# 16n_13.net
KiCad netlist of a schematic drawn in EAGLE
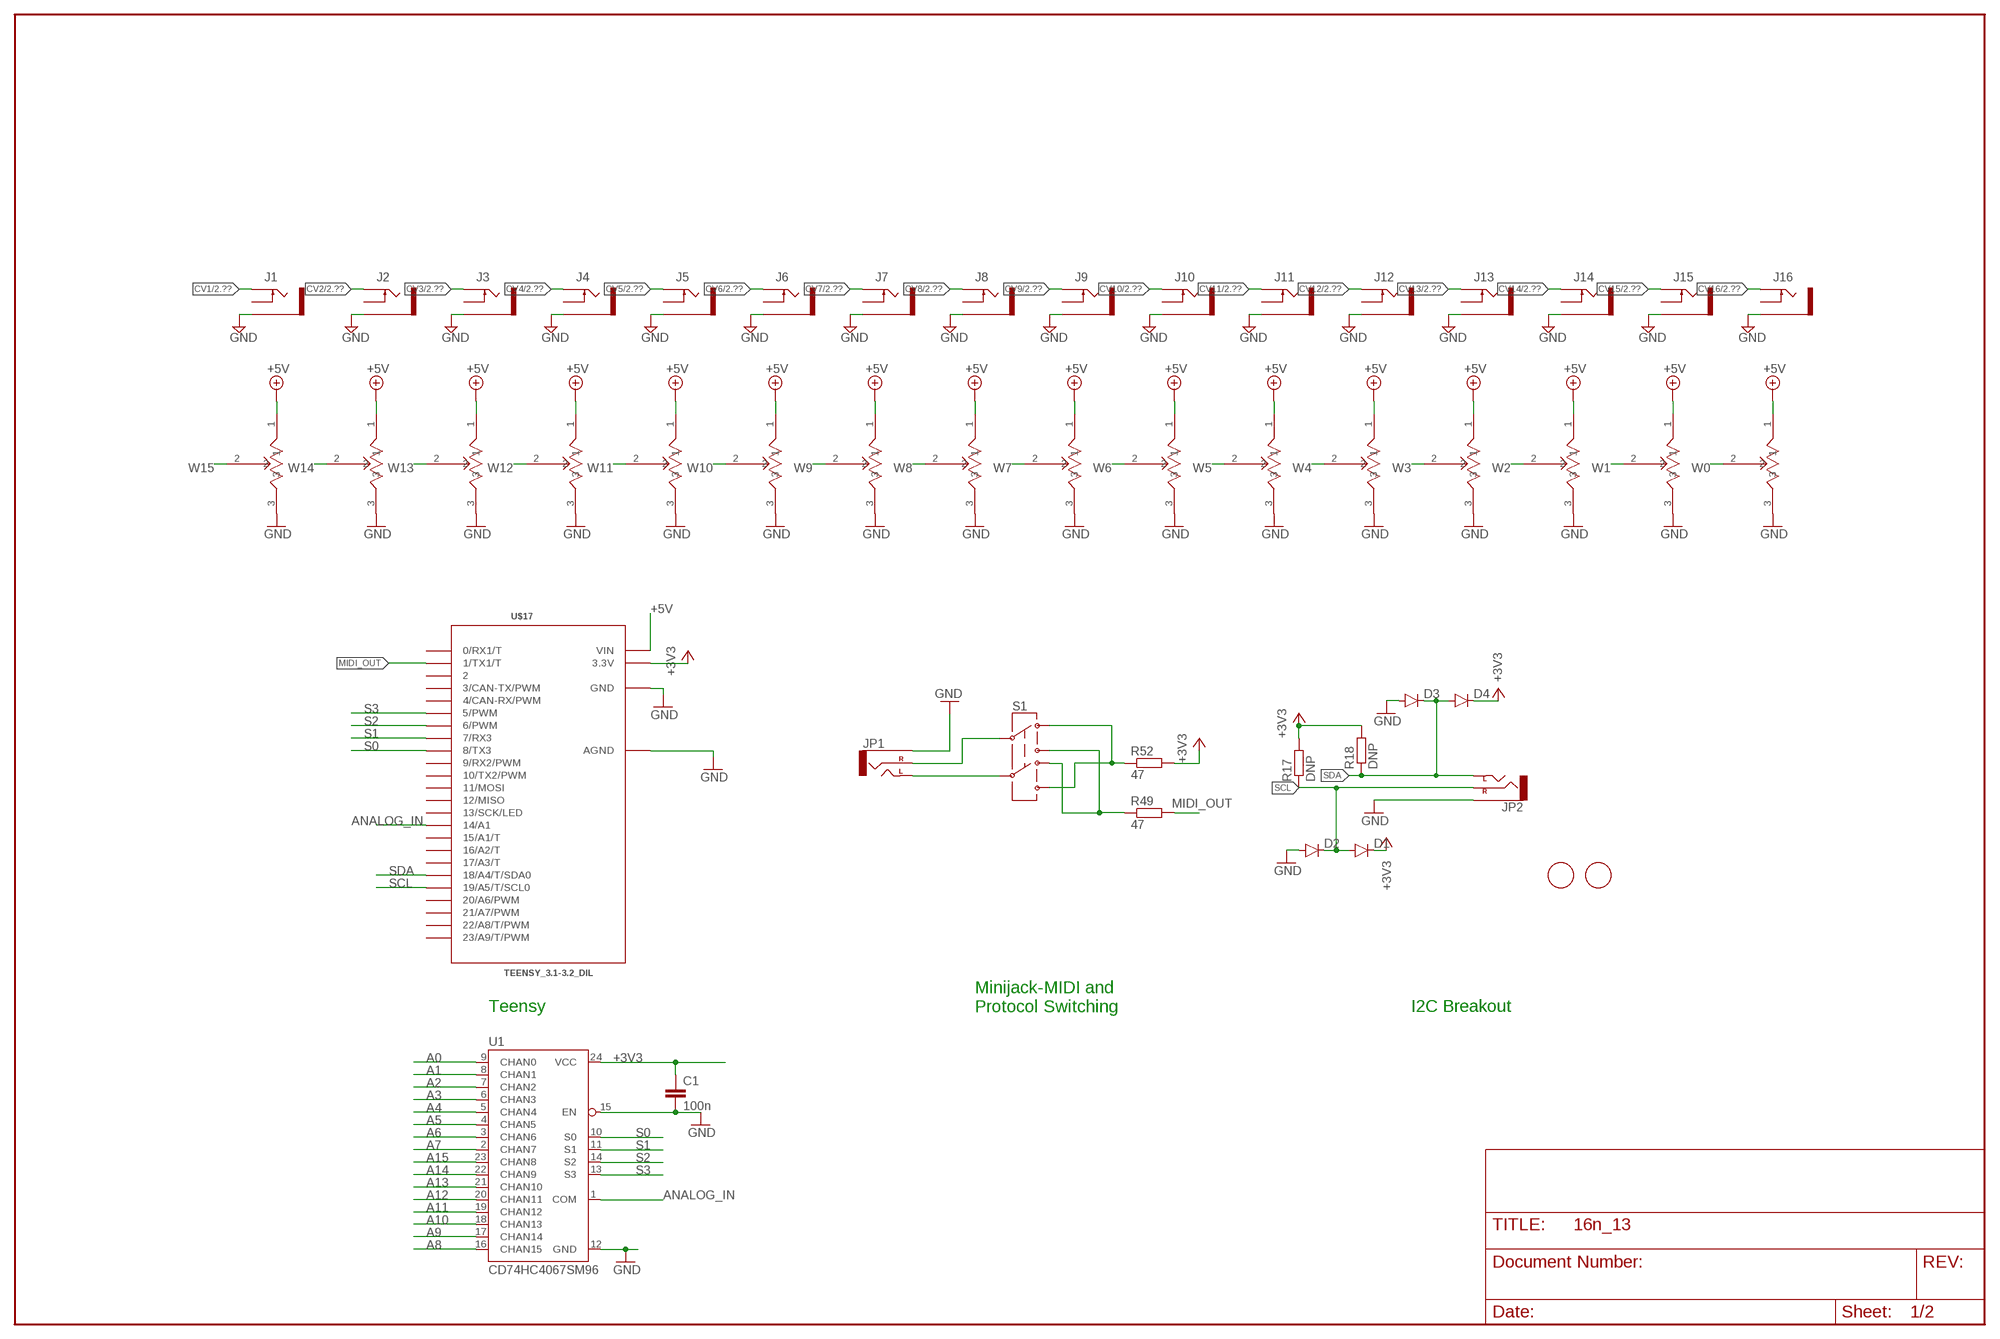
[diagram p0: schematic, sheet 1]
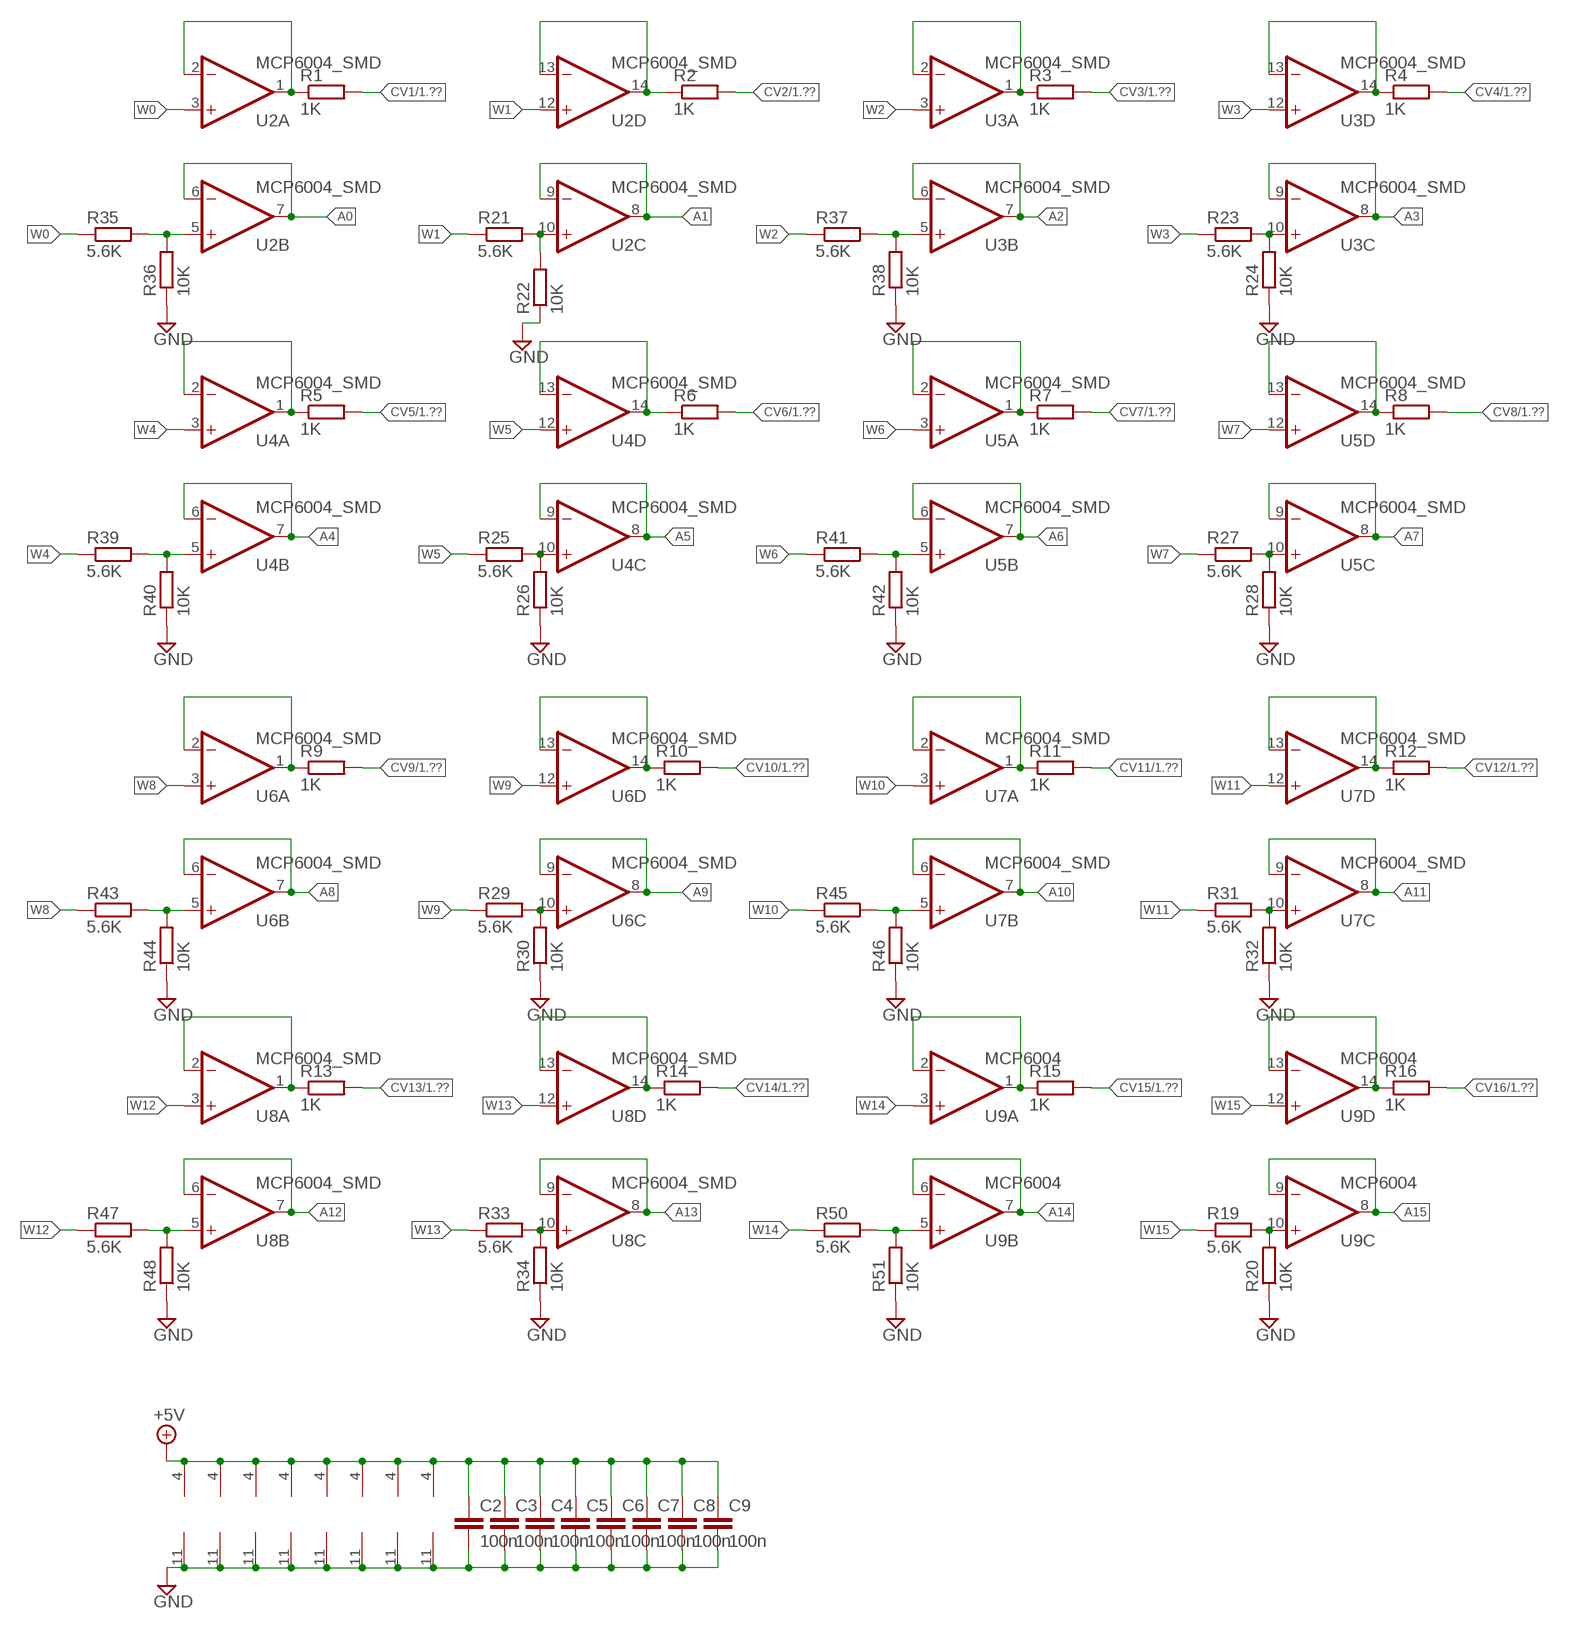
[diagram p1: schematic, sheet 2]

(export (version "E")
  (design (tool "Eeschema 10.0.6"))
  (components
    (comp (ref "C2")
      (value "100n")
      (footprint "eagle-import:C0805")
      (libsource (lib "eagle-import") (part "C-EUC0805"))
    )
    (comp (ref "C3")
      (value "100n")
      (footprint "eagle-import:C0805")
      (libsource (lib "eagle-import") (part "C-EUC0805"))
    )
    (comp (ref "C4")
      (value "100n")
      (footprint "eagle-import:C0805")
      (libsource (lib "eagle-import") (part "C-EUC0805"))
    )
    (comp (ref "C5")
      (value "100n")
      (footprint "eagle-import:C0805")
      (libsource (lib "eagle-import") (part "C-EUC0805"))
    )
    (comp (ref "C6")
      (value "100n")
      (footprint "eagle-import:C0805")
      (libsource (lib "eagle-import") (part "C-EUC0805"))
    )
    (comp (ref "C7")
      (value "100n")
      (footprint "eagle-import:C0805")
      (libsource (lib "eagle-import") (part "C-EUC0805"))
    )
    (comp (ref "C8")
      (value "100n")
      (footprint "eagle-import:C0805")
      (libsource (lib "eagle-import") (part "C-EUC0805"))
    )
    (comp (ref "C9")
      (value "100n")
      (footprint "eagle-import:C0805")
      (libsource (lib "eagle-import") (part "C-EUC0805"))
    )
    (comp (ref "R1")
      (value "1K")
      (footprint "eagle-import:R0805")
      (libsource (lib "eagle-import") (part "R-EU_R0805"))
    )
    (comp (ref "R2")
      (value "1K")
      (footprint "eagle-import:R0805")
      (libsource (lib "eagle-import") (part "R-EU_R0805"))
    )
    (comp (ref "R3")
      (value "1K")
      (footprint "eagle-import:R0805")
      (libsource (lib "eagle-import") (part "R-EU_R0805"))
    )
    (comp (ref "R4")
      (value "1K")
      (footprint "eagle-import:R0805")
      (libsource (lib "eagle-import") (part "R-EU_R0805"))
    )
    (comp (ref "R5")
      (value "1K")
      (footprint "eagle-import:R0805")
      (libsource (lib "eagle-import") (part "R-EU_R0805"))
    )
    (comp (ref "R6")
      (value "1K")
      (footprint "eagle-import:R0805")
      (libsource (lib "eagle-import") (part "R-EU_R0805"))
    )
    (comp (ref "R7")
      (value "1K")
      (footprint "eagle-import:R0805")
      (libsource (lib "eagle-import") (part "R-EU_R0805"))
    )
    (comp (ref "R8")
      (value "1K")
      (footprint "eagle-import:R0805")
      (libsource (lib "eagle-import") (part "R-EU_R0805"))
    )
    (comp (ref "R9")
      (value "1K")
      (footprint "eagle-import:R0805")
      (libsource (lib "eagle-import") (part "R-EU_R0805"))
    )
    (comp (ref "R10")
      (value "1K")
      (footprint "eagle-import:R0805")
      (libsource (lib "eagle-import") (part "R-EU_R0805"))
    )
    (comp (ref "R11")
      (value "1K")
      (footprint "eagle-import:R0805")
      (libsource (lib "eagle-import") (part "R-EU_R0805"))
    )
    (comp (ref "R12")
      (value "1K")
      (footprint "eagle-import:R0805")
      (libsource (lib "eagle-import") (part "R-EU_R0805"))
    )
    (comp (ref "R13")
      (value "1K")
      (footprint "eagle-import:R0805")
      (libsource (lib "eagle-import") (part "R-EU_R0805"))
    )
    (comp (ref "R14")
      (value "1K")
      (footprint "eagle-import:R0805")
      (libsource (lib "eagle-import") (part "R-EU_R0805"))
    )
    (comp (ref "R15")
      (value "1K")
      (footprint "eagle-import:R0805")
      (libsource (lib "eagle-import") (part "R-EU_R0805"))
    )
    (comp (ref "R16")
      (value "1K")
      (footprint "eagle-import:R0805")
      (libsource (lib "eagle-import") (part "R-EU_R0805"))
    )
    (comp (ref "R19")
      (value "5.6K")
      (footprint "eagle-import:R0805")
      (libsource (lib "eagle-import") (part "R-EU_R0805"))
    )
    (comp (ref "R20")
      (value "10K")
      (footprint "eagle-import:R0805")
      (libsource (lib "eagle-import") (part "R-EU_R0805"))
    )
    (comp (ref "R21")
      (value "5.6K")
      (footprint "eagle-import:R0805")
      (libsource (lib "eagle-import") (part "R-EU_R0805"))
    )
    (comp (ref "R22")
      (value "10K")
      (footprint "eagle-import:R0805")
      (libsource (lib "eagle-import") (part "R-EU_R0805"))
    )
    (comp (ref "R23")
      (value "5.6K")
      (footprint "eagle-import:R0805")
      (libsource (lib "eagle-import") (part "R-EU_R0805"))
    )
    (comp (ref "R24")
      (value "10K")
      (footprint "eagle-import:R0805")
      (libsource (lib "eagle-import") (part "R-EU_R0805"))
    )
    (comp (ref "R25")
      (value "5.6K")
      (footprint "eagle-import:R0805")
      (libsource (lib "eagle-import") (part "R-EU_R0805"))
    )
    (comp (ref "R26")
      (value "10K")
      (footprint "eagle-import:R0805")
      (libsource (lib "eagle-import") (part "R-EU_R0805"))
    )
    (comp (ref "R27")
      (value "5.6K")
      (footprint "eagle-import:R0805")
      (libsource (lib "eagle-import") (part "R-EU_R0805"))
    )
    (comp (ref "R28")
      (value "10K")
      (footprint "eagle-import:R0805")
      (libsource (lib "eagle-import") (part "R-EU_R0805"))
    )
    (comp (ref "R29")
      (value "5.6K")
      (footprint "eagle-import:R0805")
      (libsource (lib "eagle-import") (part "R-EU_R0805"))
    )
    (comp (ref "R30")
      (value "10K")
      (footprint "eagle-import:R0805")
      (libsource (lib "eagle-import") (part "R-EU_R0805"))
    )
    (comp (ref "R31")
      (value "5.6K")
      (footprint "eagle-import:R0805")
      (libsource (lib "eagle-import") (part "R-EU_R0805"))
    )
    (comp (ref "R32")
      (value "10K")
      (footprint "eagle-import:R0805")
      (libsource (lib "eagle-import") (part "R-EU_R0805"))
    )
    (comp (ref "R33")
      (value "5.6K")
      (footprint "eagle-import:R0805")
      (libsource (lib "eagle-import") (part "R-EU_R0805"))
    )
    (comp (ref "R34")
      (value "10K")
      (footprint "eagle-import:R0805")
      (libsource (lib "eagle-import") (part "R-EU_R0805"))
    )
    (comp (ref "R35")
      (value "5.6K")
      (footprint "eagle-import:R0805")
      (libsource (lib "eagle-import") (part "R-EU_R0805"))
    )
    (comp (ref "R36")
      (value "10K")
      (footprint "eagle-import:R0805")
      (libsource (lib "eagle-import") (part "R-EU_R0805"))
    )
    (comp (ref "R37")
      (value "5.6K")
      (footprint "eagle-import:R0805")
      (libsource (lib "eagle-import") (part "R-EU_R0805"))
    )
    (comp (ref "R38")
      (value "10K")
      (footprint "eagle-import:R0805")
      (libsource (lib "eagle-import") (part "R-EU_R0805"))
    )
    (comp (ref "R39")
      (value "5.6K")
      (footprint "eagle-import:R0805")
      (libsource (lib "eagle-import") (part "R-EU_R0805"))
    )
    (comp (ref "R40")
      (value "10K")
      (footprint "eagle-import:R0805")
      (libsource (lib "eagle-import") (part "R-EU_R0805"))
    )
    (comp (ref "R41")
      (value "5.6K")
      (footprint "eagle-import:R0805")
      (libsource (lib "eagle-import") (part "R-EU_R0805"))
    )
    (comp (ref "R42")
      (value "10K")
      (footprint "eagle-import:R0805")
      (libsource (lib "eagle-import") (part "R-EU_R0805"))
    )
    (comp (ref "R43")
      (value "5.6K")
      (footprint "eagle-import:R0805")
      (libsource (lib "eagle-import") (part "R-EU_R0805"))
    )
    (comp (ref "R44")
      (value "10K")
      (footprint "eagle-import:R0805")
      (libsource (lib "eagle-import") (part "R-EU_R0805"))
    )
    (comp (ref "R45")
      (value "5.6K")
      (footprint "eagle-import:R0805")
      (libsource (lib "eagle-import") (part "R-EU_R0805"))
    )
    (comp (ref "R46")
      (value "10K")
      (footprint "eagle-import:R0805")
      (libsource (lib "eagle-import") (part "R-EU_R0805"))
    )
    (comp (ref "R47")
      (value "5.6K")
      (footprint "eagle-import:R0805")
      (libsource (lib "eagle-import") (part "R-EU_R0805"))
    )
    (comp (ref "R48")
      (value "10K")
      (footprint "eagle-import:R0805")
      (libsource (lib "eagle-import") (part "R-EU_R0805"))
    )
    (comp (ref "R50")
      (value "5.6K")
      (footprint "eagle-import:R0805")
      (libsource (lib "eagle-import") (part "R-EU_R0805"))
    )
    (comp (ref "R51")
      (value "10K")
      (footprint "eagle-import:R0805")
      (libsource (lib "eagle-import") (part "R-EU_R0805"))
    )
    (comp (ref "U2")
      (value "MCP6004_SMD")
      (footprint "eagle-import:SO14")
      (libsource (lib "eagle-import") (part "MCP6004_SMD"))
    )
    (comp (ref "U3")
      (value "MCP6004_SMD")
      (footprint "eagle-import:SO14")
      (libsource (lib "eagle-import") (part "MCP6004_SMD"))
    )
    (comp (ref "U4")
      (value "MCP6004_SMD")
      (footprint "eagle-import:SO14")
      (libsource (lib "eagle-import") (part "MCP6004_SMD"))
    )
    (comp (ref "U5")
      (value "MCP6004_SMD")
      (footprint "eagle-import:SO14")
      (libsource (lib "eagle-import") (part "MCP6004_SMD"))
    )
    (comp (ref "U6")
      (value "MCP6004_SMD")
      (footprint "eagle-import:SO14")
      (libsource (lib "eagle-import") (part "MCP6004_SMD"))
    )
    (comp (ref "U7")
      (value "MCP6004_SMD")
      (footprint "eagle-import:SO14")
      (libsource (lib "eagle-import") (part "MCP6004_SMD"))
    )
    (comp (ref "U8")
      (value "MCP6004_SMD")
      (footprint "eagle-import:SO14")
      (libsource (lib "eagle-import") (part "MCP6004_SMD"))
    )
    (comp (ref "U9")
      (value "MCP6004")
      (footprint "eagle-import:SO14")
      (libsource (lib "eagle-import") (part "MCP6004_SMD"))
    )
    (comp (ref "C1")
      (value "100n")
      (footprint "eagle-import:C0805")
      (libsource (lib "eagle-import") (part "C-EUC0805"))
    )
    (comp (ref "D1")
      (value "DIODESOD123")
      (footprint "eagle-import:SOD-123")
      (libsource (lib "eagle-import") (part "DIODESOD123"))
    )
    (comp (ref "D2")
      (value "DIODESOD123")
      (footprint "eagle-import:SOD-123")
      (libsource (lib "eagle-import") (part "DIODESOD123"))
    )
    (comp (ref "D3")
      (value "DIODESOD123")
      (footprint "eagle-import:SOD-123")
      (libsource (lib "eagle-import") (part "DIODESOD123"))
    )
    (comp (ref "D4")
      (value "DIODESOD123")
      (footprint "eagle-import:SOD-123")
      (libsource (lib "eagle-import") (part "DIODESOD123"))
    )
    (comp (ref "FID1")
      (value "FIDUCIAL")
      (footprint "eagle-import:FIDUCIAL_1MM")
      (libsource (lib "eagle-import") (part "FIDUCIAL"))
    )
    (comp (ref "FID2")
      (value "FIDUCIAL")
      (footprint "eagle-import:FIDUCIAL_1MM")
      (libsource (lib "eagle-import") (part "FIDUCIAL"))
    )
    (comp (ref "J1")
      (value "PJ302M")
      (footprint "eagle-import:PJ302M")
      (libsource (lib "eagle-import") (part "PJ302M"))
    )
    (comp (ref "J2")
      (value "PJ302M")
      (footprint "eagle-import:PJ302M")
      (libsource (lib "eagle-import") (part "PJ302M"))
    )
    (comp (ref "J3")
      (value "PJ302M")
      (footprint "eagle-import:PJ302M")
      (libsource (lib "eagle-import") (part "PJ302M"))
    )
    (comp (ref "J4")
      (value "PJ302M")
      (footprint "eagle-import:PJ302M")
      (libsource (lib "eagle-import") (part "PJ302M"))
    )
    (comp (ref "J5")
      (value "PJ302M")
      (footprint "eagle-import:PJ302M")
      (libsource (lib "eagle-import") (part "PJ302M"))
    )
    (comp (ref "J6")
      (value "PJ302M")
      (footprint "eagle-import:PJ302M")
      (libsource (lib "eagle-import") (part "PJ302M"))
    )
    (comp (ref "J7")
      (value "PJ302M")
      (footprint "eagle-import:PJ302M")
      (libsource (lib "eagle-import") (part "PJ302M"))
    )
    (comp (ref "J8")
      (value "PJ302M")
      (footprint "eagle-import:PJ302M")
      (libsource (lib "eagle-import") (part "PJ302M"))
    )
    (comp (ref "J9")
      (value "PJ302M")
      (footprint "eagle-import:PJ302M")
      (libsource (lib "eagle-import") (part "PJ302M"))
    )
    (comp (ref "J10")
      (value "PJ302M")
      (footprint "eagle-import:PJ302M")
      (libsource (lib "eagle-import") (part "PJ302M"))
    )
    (comp (ref "J11")
      (value "PJ302M")
      (footprint "eagle-import:PJ302M")
      (libsource (lib "eagle-import") (part "PJ302M"))
    )
    (comp (ref "J12")
      (value "PJ302M")
      (footprint "eagle-import:PJ302M")
      (libsource (lib "eagle-import") (part "PJ302M"))
    )
    (comp (ref "J13")
      (value "PJ302M")
      (footprint "eagle-import:PJ302M")
      (libsource (lib "eagle-import") (part "PJ302M"))
    )
    (comp (ref "J14")
      (value "PJ302M")
      (footprint "eagle-import:PJ302M")
      (libsource (lib "eagle-import") (part "PJ302M"))
    )
    (comp (ref "J15")
      (value "PJ302M")
      (footprint "eagle-import:PJ302M")
      (libsource (lib "eagle-import") (part "PJ302M"))
    )
    (comp (ref "J16")
      (value "PJ302M")
      (footprint "eagle-import:PJ302M")
      (libsource (lib "eagle-import") (part "PJ302M"))
    )
    (comp (ref "JP1")
      (value "AUDIO-JACKPTH")
      (footprint "eagle-import:AUDIO-JACK")
      (libsource (lib "eagle-import") (part "AUDIO-JACKPTH"))
    )
    (comp (ref "JP2")
      (value "AUDIO-JACKPTH")
      (footprint "eagle-import:AUDIO-JACK")
      (libsource (lib "eagle-import") (part "AUDIO-JACKPTH"))
    )
    (comp (ref "R17")
      (value "DNP")
      (footprint "eagle-import:R0805")
      (libsource (lib "eagle-import") (part "R-EU_R0805"))
    )
    (comp (ref "R18")
      (value "DNP")
      (footprint "eagle-import:R0805")
      (libsource (lib "eagle-import") (part "R-EU_R0805"))
    )
    (comp (ref "R49")
      (value "47")
      (footprint "eagle-import:R0805")
      (libsource (lib "eagle-import") (part "R-EU_R0805"))
    )
    (comp (ref "R52")
      (value "47")
      (footprint "eagle-import:R0805")
      (libsource (lib "eagle-import") (part "R-EU_R0805"))
    )
    (comp (ref "S1")
      (value "SWITCH-DPDTEG2211")
      (footprint "eagle-import:EG2211")
      (libsource (lib "eagle-import") (part "SWITCH-DPDTEG2211"))
    )
    (comp (ref "U$1")
      (value "SLIDEPOT-ALPS-60MM")
      (footprint "eagle-import:RS6011SP600")
      (libsource (lib "eagle-import") (part "SLIDEPOT-ALPS-60MM"))
    )
    (comp (ref "U$2")
      (value "SLIDEPOT-ALPS-60MM")
      (footprint "eagle-import:RS6011SP600")
      (libsource (lib "eagle-import") (part "SLIDEPOT-ALPS-60MM"))
    )
    (comp (ref "U$3")
      (value "SLIDEPOT-ALPS-60MM")
      (footprint "eagle-import:RS6011SP600")
      (libsource (lib "eagle-import") (part "SLIDEPOT-ALPS-60MM"))
    )
    (comp (ref "U$4")
      (value "SLIDEPOT-ALPS-60MM")
      (footprint "eagle-import:RS6011SP600")
      (libsource (lib "eagle-import") (part "SLIDEPOT-ALPS-60MM"))
    )
    (comp (ref "U$5")
      (value "SLIDEPOT-ALPS-60MM")
      (footprint "eagle-import:RS6011SP600")
      (libsource (lib "eagle-import") (part "SLIDEPOT-ALPS-60MM"))
    )
    (comp (ref "U$6")
      (value "SLIDEPOT-ALPS-60MM")
      (footprint "eagle-import:RS6011SP600")
      (libsource (lib "eagle-import") (part "SLIDEPOT-ALPS-60MM"))
    )
    (comp (ref "U$7")
      (value "SLIDEPOT-ALPS-60MM")
      (footprint "eagle-import:RS6011SP600")
      (libsource (lib "eagle-import") (part "SLIDEPOT-ALPS-60MM"))
    )
    (comp (ref "U$8")
      (value "SLIDEPOT-ALPS-60MM")
      (footprint "eagle-import:RS6011SP600")
      (libsource (lib "eagle-import") (part "SLIDEPOT-ALPS-60MM"))
    )
    (comp (ref "U$9")
      (value "SLIDEPOT-ALPS-60MM")
      (footprint "eagle-import:RS6011SP600")
      (libsource (lib "eagle-import") (part "SLIDEPOT-ALPS-60MM"))
    )
    (comp (ref "U$10")
      (value "SLIDEPOT-ALPS-60MM")
      (footprint "eagle-import:RS6011SP600")
      (libsource (lib "eagle-import") (part "SLIDEPOT-ALPS-60MM"))
    )
    (comp (ref "U$11")
      (value "SLIDEPOT-ALPS-60MM")
      (footprint "eagle-import:RS6011SP600")
      (libsource (lib "eagle-import") (part "SLIDEPOT-ALPS-60MM"))
    )
    (comp (ref "U$12")
      (value "SLIDEPOT-ALPS-60MM")
      (footprint "eagle-import:RS6011SP600")
      (libsource (lib "eagle-import") (part "SLIDEPOT-ALPS-60MM"))
    )
    (comp (ref "U$13")
      (value "SLIDEPOT-ALPS-60MM")
      (footprint "eagle-import:RS6011SP600")
      (libsource (lib "eagle-import") (part "SLIDEPOT-ALPS-60MM"))
    )
    (comp (ref "U$14")
      (value "SLIDEPOT-ALPS-60MM")
      (footprint "eagle-import:RS6011SP600")
      (libsource (lib "eagle-import") (part "SLIDEPOT-ALPS-60MM"))
    )
    (comp (ref "U$15")
      (value "SLIDEPOT-ALPS-60MM")
      (footprint "eagle-import:RS6011SP600")
      (libsource (lib "eagle-import") (part "SLIDEPOT-ALPS-60MM"))
    )
    (comp (ref "U$16")
      (value "SLIDEPOT-ALPS-60MM")
      (footprint "eagle-import:RS6011SP600")
      (libsource (lib "eagle-import") (part "SLIDEPOT-ALPS-60MM"))
    )
    (comp (ref "U$17")
      (value "TEENSY_3.1-3.2_DIL")
      (footprint "eagle-import:TEENSY_3.0-3.2&LC_DIL")
      (libsource (lib "eagle-import") (part "TEENSY_3.1-3.2_DIL"))
    )
    (comp (ref "U1")
      (value "CD74HC4067SM96")
      (footprint "eagle-import:SOIC127P1030X265-24")
      (libsource (lib "eagle-import") (part "744067SO24"))
    )
  )
  (nets
    (net (code "1") (name "+3V3") (class "Default")
      (node (ref "C1") (pin "1") (pinfunction "1_1") (pintype "passive"))
      (node (ref "D1") (pin "C") (pinfunction "C_C") (pintype "passive"))
      (node (ref "D4") (pin "C") (pinfunction "C_C") (pintype "passive"))
      (node (ref "R17") (pin "2") (pinfunction "2_2") (pintype "passive"))
      (node (ref "R18") (pin "2") (pinfunction "2_2") (pintype "passive"))
      (node (ref "R52") (pin "2") (pinfunction "2_2") (pintype "passive"))
      (node (ref "U$17") (pin "3.3V") (pinfunction "3.3V_3.3V") (pintype "power_in"))
      (node (ref "U1") (pin "24") (pinfunction "VCC_24") (pintype "bidirectional"))
    )
    (net (code "2") (name "+5V") (class "Default")
      (node (ref "C2") (pin "1") (pinfunction "1_1") (pintype "passive"))
      (node (ref "C3") (pin "1") (pinfunction "1_1") (pintype "passive"))
      (node (ref "C4") (pin "1") (pinfunction "1_1") (pintype "passive"))
      (node (ref "C5") (pin "1") (pinfunction "1_1") (pintype "passive"))
      (node (ref "C6") (pin "1") (pinfunction "1_1") (pintype "passive"))
      (node (ref "C7") (pin "1") (pinfunction "1_1") (pintype "passive"))
      (node (ref "C8") (pin "1") (pinfunction "1_1") (pintype "passive"))
      (node (ref "C9") (pin "1") (pinfunction "1_1") (pintype "passive"))
      (node (ref "U$1") (pin "1") (pinfunction "1_1") (pintype "bidirectional"))
      (node (ref "U$10") (pin "1") (pinfunction "1_1") (pintype "bidirectional"))
      (node (ref "U$11") (pin "1") (pinfunction "1_1") (pintype "bidirectional"))
      (node (ref "U$12") (pin "1") (pinfunction "1_1") (pintype "bidirectional"))
      (node (ref "U$13") (pin "1") (pinfunction "1_1") (pintype "bidirectional"))
      (node (ref "U$14") (pin "1") (pinfunction "1_1") (pintype "bidirectional"))
      (node (ref "U$15") (pin "1") (pinfunction "1_1") (pintype "bidirectional"))
      (node (ref "U$16") (pin "1") (pinfunction "1_1") (pintype "bidirectional"))
      (node (ref "U$17") (pin "VIN") (pinfunction "VIN_VIN") (pintype "power_in"))
      (node (ref "U$2") (pin "1") (pinfunction "1_1") (pintype "bidirectional"))
      (node (ref "U$3") (pin "1") (pinfunction "1_1") (pintype "bidirectional"))
      (node (ref "U$4") (pin "1") (pinfunction "1_1") (pintype "bidirectional"))
      (node (ref "U$5") (pin "1") (pinfunction "1_1") (pintype "bidirectional"))
      (node (ref "U$6") (pin "1") (pinfunction "1_1") (pintype "bidirectional"))
      (node (ref "U$7") (pin "1") (pinfunction "1_1") (pintype "bidirectional"))
      (node (ref "U$8") (pin "1") (pinfunction "1_1") (pintype "bidirectional"))
      (node (ref "U$9") (pin "1") (pinfunction "1_1") (pintype "bidirectional"))
      (node (ref "U2") (pin "4") (pinfunction "V+_4") (pintype "power_in"))
      (node (ref "U3") (pin "4") (pinfunction "V+_4") (pintype "power_in"))
      (node (ref "U4") (pin "4") (pinfunction "V+_4") (pintype "power_in"))
      (node (ref "U5") (pin "4") (pinfunction "V+_4") (pintype "power_in"))
      (node (ref "U6") (pin "4") (pinfunction "V+_4") (pintype "power_in"))
      (node (ref "U7") (pin "4") (pinfunction "V+_4") (pintype "power_in"))
      (node (ref "U8") (pin "4") (pinfunction "V+_4") (pintype "power_in"))
      (node (ref "U9") (pin "4") (pinfunction "V+_4") (pintype "power_in"))
    )
    (net (code "3") (name "A0") (class "Default")
      (node (ref "U1") (pin "9") (pinfunction "CHAN0_9") (pintype "bidirectional"))
      (node (ref "U2") (pin "6") (pinfunction "-IN_6") (pintype "input"))
      (node (ref "U2") (pin "7") (pinfunction "OUT_7") (pintype "output"))
    )
    (net (code "4") (name "A1") (class "Default")
      (node (ref "U1") (pin "8") (pinfunction "CHAN1_8") (pintype "bidirectional"))
      (node (ref "U2") (pin "8") (pinfunction "OUT_8") (pintype "output"))
      (node (ref "U2") (pin "9") (pinfunction "-IN_9") (pintype "input"))
    )
    (net (code "5") (name "A2") (class "Default")
      (node (ref "U1") (pin "7") (pinfunction "CHAN2_7") (pintype "bidirectional"))
      (node (ref "U3") (pin "6") (pinfunction "-IN_6") (pintype "input"))
      (node (ref "U3") (pin "7") (pinfunction "OUT_7") (pintype "output"))
    )
    (net (code "6") (name "A3") (class "Default")
      (node (ref "U1") (pin "6") (pinfunction "CHAN3_6") (pintype "bidirectional"))
      (node (ref "U3") (pin "8") (pinfunction "OUT_8") (pintype "output"))
      (node (ref "U3") (pin "9") (pinfunction "-IN_9") (pintype "input"))
    )
    (net (code "7") (name "A4") (class "Default")
      (node (ref "U1") (pin "5") (pinfunction "CHAN4_5") (pintype "bidirectional"))
      (node (ref "U4") (pin "6") (pinfunction "-IN_6") (pintype "input"))
      (node (ref "U4") (pin "7") (pinfunction "OUT_7") (pintype "output"))
    )
    (net (code "8") (name "A5") (class "Default")
      (node (ref "U1") (pin "4") (pinfunction "CHAN5_4") (pintype "bidirectional"))
      (node (ref "U4") (pin "8") (pinfunction "OUT_8") (pintype "output"))
      (node (ref "U4") (pin "9") (pinfunction "-IN_9") (pintype "input"))
    )
    (net (code "9") (name "A6") (class "Default")
      (node (ref "U1") (pin "3") (pinfunction "CHAN6_3") (pintype "bidirectional"))
      (node (ref "U5") (pin "6") (pinfunction "-IN_6") (pintype "input"))
      (node (ref "U5") (pin "7") (pinfunction "OUT_7") (pintype "output"))
    )
    (net (code "10") (name "A7") (class "Default")
      (node (ref "U1") (pin "2") (pinfunction "CHAN7_2") (pintype "bidirectional"))
      (node (ref "U5") (pin "8") (pinfunction "OUT_8") (pintype "output"))
      (node (ref "U5") (pin "9") (pinfunction "-IN_9") (pintype "input"))
    )
    (net (code "11") (name "A8") (class "Default")
      (node (ref "U1") (pin "16") (pinfunction "CHAN15_16") (pintype "bidirectional"))
      (node (ref "U6") (pin "6") (pinfunction "-IN_6") (pintype "input"))
      (node (ref "U6") (pin "7") (pinfunction "OUT_7") (pintype "output"))
    )
    (net (code "12") (name "A9") (class "Default")
      (node (ref "U1") (pin "17") (pinfunction "CHAN14_17") (pintype "bidirectional"))
      (node (ref "U6") (pin "8") (pinfunction "OUT_8") (pintype "output"))
      (node (ref "U6") (pin "9") (pinfunction "-IN_9") (pintype "input"))
    )
    (net (code "13") (name "A10") (class "Default")
      (node (ref "U1") (pin "18") (pinfunction "CHAN13_18") (pintype "bidirectional"))
      (node (ref "U7") (pin "6") (pinfunction "-IN_6") (pintype "input"))
      (node (ref "U7") (pin "7") (pinfunction "OUT_7") (pintype "output"))
    )
    (net (code "14") (name "A11") (class "Default")
      (node (ref "U1") (pin "19") (pinfunction "CHAN12_19") (pintype "bidirectional"))
      (node (ref "U7") (pin "8") (pinfunction "OUT_8") (pintype "output"))
      (node (ref "U7") (pin "9") (pinfunction "-IN_9") (pintype "input"))
    )
    (net (code "15") (name "A12") (class "Default")
      (node (ref "U1") (pin "20") (pinfunction "CHAN11_20") (pintype "bidirectional"))
      (node (ref "U8") (pin "6") (pinfunction "-IN_6") (pintype "input"))
      (node (ref "U8") (pin "7") (pinfunction "OUT_7") (pintype "output"))
    )
    (net (code "16") (name "A13") (class "Default")
      (node (ref "U1") (pin "21") (pinfunction "CHAN10_21") (pintype "bidirectional"))
      (node (ref "U8") (pin "8") (pinfunction "OUT_8") (pintype "output"))
      (node (ref "U8") (pin "9") (pinfunction "-IN_9") (pintype "input"))
    )
    (net (code "17") (name "A14") (class "Default")
      (node (ref "U1") (pin "22") (pinfunction "CHAN9_22") (pintype "bidirectional"))
      (node (ref "U9") (pin "6") (pinfunction "-IN_6") (pintype "input"))
      (node (ref "U9") (pin "7") (pinfunction "OUT_7") (pintype "output"))
    )
    (net (code "18") (name "A15") (class "Default")
      (node (ref "U1") (pin "23") (pinfunction "CHAN8_23") (pintype "bidirectional"))
      (node (ref "U9") (pin "8") (pinfunction "OUT_8") (pintype "output"))
      (node (ref "U9") (pin "9") (pinfunction "-IN_9") (pintype "input"))
    )
    (net (code "19") (name "ANALOG_IN") (class "Default")
      (node (ref "U$17") (pin "14/A0") (pinfunction "14/A1_14/A0") (pintype "bidirectional"))
      (node (ref "U1") (pin "1") (pinfunction "COM_1") (pintype "bidirectional"))
    )
    (net (code "20") (name "CV1") (class "Default")
      (node (ref "J1") (pin "TIP") (pinfunction "TIP_TIP") (pintype "passive"))
      (node (ref "R1") (pin "2") (pinfunction "2_2") (pintype "passive"))
    )
    (net (code "21") (name "CV2") (class "Default")
      (node (ref "J2") (pin "TIP") (pinfunction "TIP_TIP") (pintype "passive"))
      (node (ref "R2") (pin "2") (pinfunction "2_2") (pintype "passive"))
    )
    (net (code "22") (name "CV3") (class "Default")
      (node (ref "J3") (pin "TIP") (pinfunction "TIP_TIP") (pintype "passive"))
      (node (ref "R3") (pin "2") (pinfunction "2_2") (pintype "passive"))
    )
    (net (code "23") (name "CV4") (class "Default")
      (node (ref "J4") (pin "TIP") (pinfunction "TIP_TIP") (pintype "passive"))
      (node (ref "R4") (pin "2") (pinfunction "2_2") (pintype "passive"))
    )
    (net (code "24") (name "CV5") (class "Default")
      (node (ref "J5") (pin "TIP") (pinfunction "TIP_TIP") (pintype "passive"))
      (node (ref "R5") (pin "2") (pinfunction "2_2") (pintype "passive"))
    )
    (net (code "25") (name "CV6") (class "Default")
      (node (ref "J6") (pin "TIP") (pinfunction "TIP_TIP") (pintype "passive"))
      (node (ref "R6") (pin "2") (pinfunction "2_2") (pintype "passive"))
    )
    (net (code "26") (name "CV7") (class "Default")
      (node (ref "J7") (pin "TIP") (pinfunction "TIP_TIP") (pintype "passive"))
      (node (ref "R7") (pin "2") (pinfunction "2_2") (pintype "passive"))
    )
    (net (code "27") (name "CV8") (class "Default")
      (node (ref "J8") (pin "TIP") (pinfunction "TIP_TIP") (pintype "passive"))
      (node (ref "R8") (pin "2") (pinfunction "2_2") (pintype "passive"))
    )
    (net (code "28") (name "CV9") (class "Default")
      (node (ref "J9") (pin "TIP") (pinfunction "TIP_TIP") (pintype "passive"))
      (node (ref "R9") (pin "2") (pinfunction "2_2") (pintype "passive"))
    )
    (net (code "29") (name "CV10") (class "Default")
      (node (ref "J10") (pin "TIP") (pinfunction "TIP_TIP") (pintype "passive"))
      (node (ref "R10") (pin "2") (pinfunction "2_2") (pintype "passive"))
    )
    (net (code "30") (name "CV11") (class "Default")
      (node (ref "J11") (pin "TIP") (pinfunction "TIP_TIP") (pintype "passive"))
      (node (ref "R11") (pin "2") (pinfunction "2_2") (pintype "passive"))
    )
    (net (code "31") (name "CV12") (class "Default")
      (node (ref "J12") (pin "TIP") (pinfunction "TIP_TIP") (pintype "passive"))
      (node (ref "R12") (pin "2") (pinfunction "2_2") (pintype "passive"))
    )
    (net (code "32") (name "CV13") (class "Default")
      (node (ref "J13") (pin "TIP") (pinfunction "TIP_TIP") (pintype "passive"))
      (node (ref "R13") (pin "2") (pinfunction "2_2") (pintype "passive"))
    )
    (net (code "33") (name "CV14") (class "Default")
      (node (ref "J14") (pin "TIP") (pinfunction "TIP_TIP") (pintype "passive"))
      (node (ref "R14") (pin "2") (pinfunction "2_2") (pintype "passive"))
    )
    (net (code "34") (name "CV15") (class "Default")
      (node (ref "J15") (pin "TIP") (pinfunction "TIP_TIP") (pintype "passive"))
      (node (ref "R15") (pin "2") (pinfunction "2_2") (pintype "passive"))
    )
    (net (code "35") (name "CV16") (class "Default")
      (node (ref "J16") (pin "TIP") (pinfunction "TIP_TIP") (pintype "passive"))
      (node (ref "R16") (pin "2") (pinfunction "2_2") (pintype "passive"))
    )
    (net (code "36") (name "GND") (class "Default")
      (node (ref "C1") (pin "2") (pinfunction "2_2") (pintype "passive"))
      (node (ref "C2") (pin "2") (pinfunction "2_2") (pintype "passive"))
      (node (ref "C3") (pin "2") (pinfunction "2_2") (pintype "passive"))
      (node (ref "C4") (pin "2") (pinfunction "2_2") (pintype "passive"))
      (node (ref "C5") (pin "2") (pinfunction "2_2") (pintype "passive"))
      (node (ref "C6") (pin "2") (pinfunction "2_2") (pintype "passive"))
      (node (ref "C7") (pin "2") (pinfunction "2_2") (pintype "passive"))
      (node (ref "C8") (pin "2") (pinfunction "2_2") (pintype "passive"))
      (node (ref "C9") (pin "2") (pinfunction "2_2") (pintype "passive"))
      (node (ref "D2") (pin "A") (pinfunction "A_A") (pintype "passive"))
      (node (ref "D3") (pin "A") (pinfunction "A_A") (pintype "passive"))
      (node (ref "J1") (pin "GND") (pinfunction "SLEEVE_GND") (pintype "passive"))
      (node (ref "J10") (pin "GND") (pinfunction "SLEEVE_GND") (pintype "passive"))
      (node (ref "J11") (pin "GND") (pinfunction "SLEEVE_GND") (pintype "passive"))
      (node (ref "J12") (pin "GND") (pinfunction "SLEEVE_GND") (pintype "passive"))
      (node (ref "J13") (pin "GND") (pinfunction "SLEEVE_GND") (pintype "passive"))
      (node (ref "J14") (pin "GND") (pinfunction "SLEEVE_GND") (pintype "passive"))
      (node (ref "J15") (pin "GND") (pinfunction "SLEEVE_GND") (pintype "passive"))
      (node (ref "J16") (pin "GND") (pinfunction "SLEEVE_GND") (pintype "passive"))
      (node (ref "J2") (pin "GND") (pinfunction "SLEEVE_GND") (pintype "passive"))
      (node (ref "J3") (pin "GND") (pinfunction "SLEEVE_GND") (pintype "passive"))
      (node (ref "J4") (pin "GND") (pinfunction "SLEEVE_GND") (pintype "passive"))
      (node (ref "J5") (pin "GND") (pinfunction "SLEEVE_GND") (pintype "passive"))
      (node (ref "J6") (pin "GND") (pinfunction "SLEEVE_GND") (pintype "passive"))
      (node (ref "J7") (pin "GND") (pinfunction "SLEEVE_GND") (pintype "passive"))
      (node (ref "J8") (pin "GND") (pinfunction "SLEEVE_GND") (pintype "passive"))
      (node (ref "J9") (pin "GND") (pinfunction "SLEEVE_GND") (pintype "passive"))
      (node (ref "JP1") (pin "SLEEVE") (pinfunction "SLEEVE_SLEEVE") (pintype "bidirectional"))
      (node (ref "JP2") (pin "SLEEVE") (pinfunction "SLEEVE_SLEEVE") (pintype "bidirectional"))
      (node (ref "R20") (pin "1") (pinfunction "1_1") (pintype "passive"))
      (node (ref "R22") (pin "1") (pinfunction "1_1") (pintype "passive"))
      (node (ref "R24") (pin "1") (pinfunction "1_1") (pintype "passive"))
      (node (ref "R26") (pin "1") (pinfunction "1_1") (pintype "passive"))
      (node (ref "R28") (pin "1") (pinfunction "1_1") (pintype "passive"))
      (node (ref "R30") (pin "1") (pinfunction "1_1") (pintype "passive"))
      (node (ref "R32") (pin "1") (pinfunction "1_1") (pintype "passive"))
      (node (ref "R34") (pin "1") (pinfunction "1_1") (pintype "passive"))
      (node (ref "R36") (pin "1") (pinfunction "1_1") (pintype "passive"))
      (node (ref "R38") (pin "1") (pinfunction "1_1") (pintype "passive"))
      (node (ref "R40") (pin "1") (pinfunction "1_1") (pintype "passive"))
      (node (ref "R42") (pin "1") (pinfunction "1_1") (pintype "passive"))
      (node (ref "R44") (pin "1") (pinfunction "1_1") (pintype "passive"))
      (node (ref "R46") (pin "1") (pinfunction "1_1") (pintype "passive"))
      (node (ref "R48") (pin "1") (pinfunction "1_1") (pintype "passive"))
      (node (ref "R51") (pin "1") (pinfunction "1_1") (pintype "passive"))
      (node (ref "U$1") (pin "3") (pinfunction "3_3") (pintype "bidirectional"))
      (node (ref "U$10") (pin "3") (pinfunction "3_3") (pintype "bidirectional"))
      (node (ref "U$11") (pin "3") (pinfunction "3_3") (pintype "bidirectional"))
      (node (ref "U$12") (pin "3") (pinfunction "3_3") (pintype "bidirectional"))
      (node (ref "U$13") (pin "3") (pinfunction "3_3") (pintype "bidirectional"))
      (node (ref "U$14") (pin "3") (pinfunction "3_3") (pintype "bidirectional"))
      (node (ref "U$15") (pin "3") (pinfunction "3_3") (pintype "bidirectional"))
      (node (ref "U$16") (pin "3") (pinfunction "3_3") (pintype "bidirectional"))
      (node (ref "U$17") (pin "AGND") (pinfunction "AGND_AGND") (pintype "power_in"))
      (node (ref "U$17") (pin "GND") (pinfunction "GND_GND") (pintype "power_in"))
      (node (ref "U$2") (pin "3") (pinfunction "3_3") (pintype "bidirectional"))
      (node (ref "U$3") (pin "3") (pinfunction "3_3") (pintype "bidirectional"))
      (node (ref "U$4") (pin "3") (pinfunction "3_3") (pintype "bidirectional"))
      (node (ref "U$5") (pin "3") (pinfunction "3_3") (pintype "bidirectional"))
      (node (ref "U$6") (pin "3") (pinfunction "3_3") (pintype "bidirectional"))
      (node (ref "U$7") (pin "3") (pinfunction "3_3") (pintype "bidirectional"))
      (node (ref "U$8") (pin "3") (pinfunction "3_3") (pintype "bidirectional"))
      (node (ref "U$9") (pin "3") (pinfunction "3_3") (pintype "bidirectional"))
      (node (ref "U1") (pin "12") (pinfunction "GND_12") (pintype "bidirectional"))
      (node (ref "U1") (pin "15") (pinfunction "EN_15") (pintype "input"))
      (node (ref "U2") (pin "11") (pinfunction "V-_11") (pintype "power_in"))
      (node (ref "U3") (pin "11") (pinfunction "V-_11") (pintype "power_in"))
      (node (ref "U4") (pin "11") (pinfunction "V-_11") (pintype "power_in"))
      (node (ref "U5") (pin "11") (pinfunction "V-_11") (pintype "power_in"))
      (node (ref "U6") (pin "11") (pinfunction "V-_11") (pintype "power_in"))
      (node (ref "U7") (pin "11") (pinfunction "V-_11") (pintype "power_in"))
      (node (ref "U8") (pin "11") (pinfunction "V-_11") (pintype "power_in"))
      (node (ref "U9") (pin "11") (pinfunction "V-_11") (pintype "power_in"))
    )
    (net (code "37") (name "MIDI_OUT") (class "Default")
      (node (ref "R49") (pin "2") (pinfunction "2_2") (pintype "passive"))
      (node (ref "U$17") (pin "1") (pinfunction "1/TX1/T_1") (pintype "bidirectional"))
    )
    (net (code "38") (name "Net-(JP1-LEFT)") (class "Default")
      (node (ref "JP1") (pin "TIP") (pinfunction "LEFT_TIP") (pintype "bidirectional"))
      (node (ref "S1") (pin "P2") (pinfunction "5_P2") (pintype "bidirectional"))
    )
    (net (code "39") (name "Net-(JP1-RIGHT)") (class "Default")
      (node (ref "JP1") (pin "RING") (pinfunction "RIGHT_RING") (pintype "bidirectional"))
      (node (ref "S1") (pin "P1") (pinfunction "2_P1") (pintype "bidirectional"))
    )
    (net (code "40") (name "Net-(S1-1)") (class "Default")
      (node (ref "R52") (pin "1") (pinfunction "1_1") (pintype "passive"))
      (node (ref "S1") (pin "P1-TA") (pinfunction "1_P1-TA") (pintype "bidirectional"))
      (node (ref "S1") (pin "P2-TB") (pinfunction "6_P2-TB") (pintype "bidirectional"))
    )
    (net (code "41") (name "Net-(S1-3)") (class "Default")
      (node (ref "R49") (pin "1") (pinfunction "1_1") (pintype "passive"))
      (node (ref "S1") (pin "P1-TB") (pinfunction "3_P1-TB") (pintype "bidirectional"))
      (node (ref "S1") (pin "P2-TA") (pinfunction "4_P2-TA") (pintype "bidirectional"))
    )
    (net (code "42") (name "Net-(U2A--IN)") (class "Default")
      (node (ref "R1") (pin "1") (pinfunction "1_1") (pintype "passive"))
      (node (ref "U2") (pin "1") (pinfunction "OUT_1") (pintype "output"))
      (node (ref "U2") (pin "2") (pinfunction "-IN_2") (pintype "input"))
    )
    (net (code "43") (name "Net-(U2B-+IN)") (class "Default")
      (node (ref "R35") (pin "2") (pinfunction "2_2") (pintype "passive"))
      (node (ref "R36") (pin "2") (pinfunction "2_2") (pintype "passive"))
      (node (ref "U2") (pin "5") (pinfunction "+IN_5") (pintype "input"))
    )
    (net (code "44") (name "Net-(U2C-+IN)") (class "Default")
      (node (ref "R21") (pin "2") (pinfunction "2_2") (pintype "passive"))
      (node (ref "R22") (pin "2") (pinfunction "2_2") (pintype "passive"))
      (node (ref "U2") (pin "10") (pinfunction "+IN_10") (pintype "input"))
    )
    (net (code "45") (name "Net-(U2D--IN)") (class "Default")
      (node (ref "R2") (pin "1") (pinfunction "1_1") (pintype "passive"))
      (node (ref "U2") (pin "13") (pinfunction "-IN_13") (pintype "input"))
      (node (ref "U2") (pin "14") (pinfunction "OUT_14") (pintype "output"))
    )
    (net (code "46") (name "Net-(U3A--IN)") (class "Default")
      (node (ref "R3") (pin "1") (pinfunction "1_1") (pintype "passive"))
      (node (ref "U3") (pin "1") (pinfunction "OUT_1") (pintype "output"))
      (node (ref "U3") (pin "2") (pinfunction "-IN_2") (pintype "input"))
    )
    (net (code "47") (name "Net-(U3B-+IN)") (class "Default")
      (node (ref "R37") (pin "2") (pinfunction "2_2") (pintype "passive"))
      (node (ref "R38") (pin "2") (pinfunction "2_2") (pintype "passive"))
      (node (ref "U3") (pin "5") (pinfunction "+IN_5") (pintype "input"))
    )
    (net (code "48") (name "Net-(U3C-+IN)") (class "Default")
      (node (ref "R23") (pin "2") (pinfunction "2_2") (pintype "passive"))
      (node (ref "R24") (pin "2") (pinfunction "2_2") (pintype "passive"))
      (node (ref "U3") (pin "10") (pinfunction "+IN_10") (pintype "input"))
    )
    (net (code "49") (name "Net-(U3D--IN)") (class "Default")
      (node (ref "R4") (pin "1") (pinfunction "1_1") (pintype "passive"))
      (node (ref "U3") (pin "13") (pinfunction "-IN_13") (pintype "input"))
      (node (ref "U3") (pin "14") (pinfunction "OUT_14") (pintype "output"))
    )
    (net (code "50") (name "Net-(U4A--IN)") (class "Default")
      (node (ref "R5") (pin "1") (pinfunction "1_1") (pintype "passive"))
      (node (ref "U4") (pin "1") (pinfunction "OUT_1") (pintype "output"))
      (node (ref "U4") (pin "2") (pinfunction "-IN_2") (pintype "input"))
    )
    (net (code "51") (name "Net-(U4B-+IN)") (class "Default")
      (node (ref "R39") (pin "2") (pinfunction "2_2") (pintype "passive"))
      (node (ref "R40") (pin "2") (pinfunction "2_2") (pintype "passive"))
      (node (ref "U4") (pin "5") (pinfunction "+IN_5") (pintype "input"))
    )
    (net (code "52") (name "Net-(U4C-+IN)") (class "Default")
      (node (ref "R25") (pin "2") (pinfunction "2_2") (pintype "passive"))
      (node (ref "R26") (pin "2") (pinfunction "2_2") (pintype "passive"))
      (node (ref "U4") (pin "10") (pinfunction "+IN_10") (pintype "input"))
    )
    (net (code "53") (name "Net-(U4D--IN)") (class "Default")
      (node (ref "R6") (pin "1") (pinfunction "1_1") (pintype "passive"))
      (node (ref "U4") (pin "13") (pinfunction "-IN_13") (pintype "input"))
      (node (ref "U4") (pin "14") (pinfunction "OUT_14") (pintype "output"))
    )
    (net (code "54") (name "Net-(U5A--IN)") (class "Default")
      (node (ref "R7") (pin "1") (pinfunction "1_1") (pintype "passive"))
      (node (ref "U5") (pin "1") (pinfunction "OUT_1") (pintype "output"))
      (node (ref "U5") (pin "2") (pinfunction "-IN_2") (pintype "input"))
    )
    (net (code "55") (name "Net-(U5B-+IN)") (class "Default")
      (node (ref "R41") (pin "2") (pinfunction "2_2") (pintype "passive"))
      (node (ref "R42") (pin "2") (pinfunction "2_2") (pintype "passive"))
      (node (ref "U5") (pin "5") (pinfunction "+IN_5") (pintype "input"))
    )
    (net (code "56") (name "Net-(U5C-+IN)") (class "Default")
      (node (ref "R27") (pin "2") (pinfunction "2_2") (pintype "passive"))
      (node (ref "R28") (pin "2") (pinfunction "2_2") (pintype "passive"))
      (node (ref "U5") (pin "10") (pinfunction "+IN_10") (pintype "input"))
    )
    (net (code "57") (name "Net-(U5D--IN)") (class "Default")
      (node (ref "R8") (pin "1") (pinfunction "1_1") (pintype "passive"))
      (node (ref "U5") (pin "13") (pinfunction "-IN_13") (pintype "input"))
      (node (ref "U5") (pin "14") (pinfunction "OUT_14") (pintype "output"))
    )
    (net (code "58") (name "Net-(U6A--IN)") (class "Default")
      (node (ref "R9") (pin "1") (pinfunction "1_1") (pintype "passive"))
      (node (ref "U6") (pin "1") (pinfunction "OUT_1") (pintype "output"))
      (node (ref "U6") (pin "2") (pinfunction "-IN_2") (pintype "input"))
    )
    (net (code "59") (name "Net-(U6B-+IN)") (class "Default")
      (node (ref "R43") (pin "2") (pinfunction "2_2") (pintype "passive"))
      (node (ref "R44") (pin "2") (pinfunction "2_2") (pintype "passive"))
      (node (ref "U6") (pin "5") (pinfunction "+IN_5") (pintype "input"))
    )
    (net (code "60") (name "Net-(U6C-+IN)") (class "Default")
      (node (ref "R29") (pin "2") (pinfunction "2_2") (pintype "passive"))
      (node (ref "R30") (pin "2") (pinfunction "2_2") (pintype "passive"))
      (node (ref "U6") (pin "10") (pinfunction "+IN_10") (pintype "input"))
    )
    (net (code "61") (name "Net-(U6D--IN)") (class "Default")
      (node (ref "R10") (pin "1") (pinfunction "1_1") (pintype "passive"))
      (node (ref "U6") (pin "13") (pinfunction "-IN_13") (pintype "input"))
      (node (ref "U6") (pin "14") (pinfunction "OUT_14") (pintype "output"))
    )
    (net (code "62") (name "Net-(U7A--IN)") (class "Default")
      (node (ref "R11") (pin "1") (pinfunction "1_1") (pintype "passive"))
      (node (ref "U7") (pin "1") (pinfunction "OUT_1") (pintype "output"))
      (node (ref "U7") (pin "2") (pinfunction "-IN_2") (pintype "input"))
    )
    (net (code "63") (name "Net-(U7B-+IN)") (class "Default")
      (node (ref "R45") (pin "2") (pinfunction "2_2") (pintype "passive"))
      (node (ref "R46") (pin "2") (pinfunction "2_2") (pintype "passive"))
      (node (ref "U7") (pin "5") (pinfunction "+IN_5") (pintype "input"))
    )
    (net (code "64") (name "Net-(U7C-+IN)") (class "Default")
      (node (ref "R31") (pin "2") (pinfunction "2_2") (pintype "passive"))
      (node (ref "R32") (pin "2") (pinfunction "2_2") (pintype "passive"))
      (node (ref "U7") (pin "10") (pinfunction "+IN_10") (pintype "input"))
    )
    (net (code "65") (name "Net-(U7D--IN)") (class "Default")
      (node (ref "R12") (pin "1") (pinfunction "1_1") (pintype "passive"))
      (node (ref "U7") (pin "13") (pinfunction "-IN_13") (pintype "input"))
      (node (ref "U7") (pin "14") (pinfunction "OUT_14") (pintype "output"))
    )
    (net (code "66") (name "Net-(U8A--IN)") (class "Default")
      (node (ref "R13") (pin "1") (pinfunction "1_1") (pintype "passive"))
      (node (ref "U8") (pin "1") (pinfunction "OUT_1") (pintype "output"))
      (node (ref "U8") (pin "2") (pinfunction "-IN_2") (pintype "input"))
    )
    (net (code "67") (name "Net-(U8B-+IN)") (class "Default")
      (node (ref "R47") (pin "2") (pinfunction "2_2") (pintype "passive"))
      (node (ref "R48") (pin "2") (pinfunction "2_2") (pintype "passive"))
      (node (ref "U8") (pin "5") (pinfunction "+IN_5") (pintype "input"))
    )
    (net (code "68") (name "Net-(U8C-+IN)") (class "Default")
      (node (ref "R33") (pin "2") (pinfunction "2_2") (pintype "passive"))
      (node (ref "R34") (pin "2") (pinfunction "2_2") (pintype "passive"))
      (node (ref "U8") (pin "10") (pinfunction "+IN_10") (pintype "input"))
    )
    (net (code "69") (name "Net-(U8D--IN)") (class "Default")
      (node (ref "R14") (pin "1") (pinfunction "1_1") (pintype "passive"))
      (node (ref "U8") (pin "13") (pinfunction "-IN_13") (pintype "input"))
      (node (ref "U8") (pin "14") (pinfunction "OUT_14") (pintype "output"))
    )
    (net (code "70") (name "Net-(U9A--IN)") (class "Default")
      (node (ref "R15") (pin "1") (pinfunction "1_1") (pintype "passive"))
      (node (ref "U9") (pin "1") (pinfunction "OUT_1") (pintype "output"))
      (node (ref "U9") (pin "2") (pinfunction "-IN_2") (pintype "input"))
    )
    (net (code "71") (name "Net-(U9B-+IN)") (class "Default")
      (node (ref "R50") (pin "2") (pinfunction "2_2") (pintype "passive"))
      (node (ref "R51") (pin "2") (pinfunction "2_2") (pintype "passive"))
      (node (ref "U9") (pin "5") (pinfunction "+IN_5") (pintype "input"))
    )
    (net (code "72") (name "Net-(U9C-+IN)") (class "Default")
      (node (ref "R19") (pin "2") (pinfunction "2_2") (pintype "passive"))
      (node (ref "R20") (pin "2") (pinfunction "2_2") (pintype "passive"))
      (node (ref "U9") (pin "10") (pinfunction "+IN_10") (pintype "input"))
    )
    (net (code "73") (name "Net-(U9D--IN)") (class "Default")
      (node (ref "R16") (pin "1") (pinfunction "1_1") (pintype "passive"))
      (node (ref "U9") (pin "13") (pinfunction "-IN_13") (pintype "input"))
      (node (ref "U9") (pin "14") (pinfunction "OUT_14") (pintype "output"))
    )
    (net (code "74") (name "S0") (class "Default")
      (node (ref "U$17") (pin "8") (pinfunction "8/TX3_8") (pintype "bidirectional"))
      (node (ref "U1") (pin "10") (pinfunction "S0_10") (pintype "input"))
    )
    (net (code "75") (name "S1") (class "Default")
      (node (ref "U$17") (pin "7") (pinfunction "7/RX3_7") (pintype "bidirectional"))
      (node (ref "U1") (pin "11") (pinfunction "S1_11") (pintype "input"))
    )
    (net (code "76") (name "S2") (class "Default")
      (node (ref "U$17") (pin "6") (pinfunction "6/PWM_6") (pintype "bidirectional"))
      (node (ref "U1") (pin "14") (pinfunction "S2_14") (pintype "input"))
    )
    (net (code "77") (name "S3") (class "Default")
      (node (ref "U$17") (pin "5") (pinfunction "5/PWM_5") (pintype "bidirectional"))
      (node (ref "U1") (pin "13") (pinfunction "S3_13") (pintype "input"))
    )
    (net (code "78") (name "SCL") (class "Default")
      (node (ref "D1") (pin "A") (pinfunction "A_A") (pintype "passive"))
      (node (ref "D2") (pin "C") (pinfunction "C_C") (pintype "passive"))
      (node (ref "JP2") (pin "RING") (pinfunction "RIGHT_RING") (pintype "bidirectional"))
      (node (ref "R17") (pin "1") (pinfunction "1_1") (pintype "passive"))
      (node (ref "U$17") (pin "19/A5") (pinfunction "19/A5/T/SCL0_19/A5") (pintype "bidirectional"))
    )
    (net (code "79") (name "SDA") (class "Default")
      (node (ref "D3") (pin "C") (pinfunction "C_C") (pintype "passive"))
      (node (ref "D4") (pin "A") (pinfunction "A_A") (pintype "passive"))
      (node (ref "JP2") (pin "TIP") (pinfunction "LEFT_TIP") (pintype "bidirectional"))
      (node (ref "R18") (pin "1") (pinfunction "1_1") (pintype "passive"))
      (node (ref "U$17") (pin "18/A4") (pinfunction "18/A4/T/SDA0_18/A4") (pintype "bidirectional"))
    )
    (net (code "80") (name "W0") (class "Default")
      (node (ref "R35") (pin "1") (pinfunction "1_1") (pintype "passive"))
      (node (ref "U$1") (pin "2") (pinfunction "2_2") (pintype "bidirectional"))
      (node (ref "U2") (pin "3") (pinfunction "+IN_3") (pintype "input"))
    )
    (net (code "81") (name "W1") (class "Default")
      (node (ref "R21") (pin "1") (pinfunction "1_1") (pintype "passive"))
      (node (ref "U$2") (pin "2") (pinfunction "2_2") (pintype "bidirectional"))
      (node (ref "U2") (pin "12") (pinfunction "+IN_12") (pintype "input"))
    )
    (net (code "82") (name "W2") (class "Default")
      (node (ref "R37") (pin "1") (pinfunction "1_1") (pintype "passive"))
      (node (ref "U$3") (pin "2") (pinfunction "2_2") (pintype "bidirectional"))
      (node (ref "U3") (pin "3") (pinfunction "+IN_3") (pintype "input"))
    )
    (net (code "83") (name "W3") (class "Default")
      (node (ref "R23") (pin "1") (pinfunction "1_1") (pintype "passive"))
      (node (ref "U$4") (pin "2") (pinfunction "2_2") (pintype "bidirectional"))
      (node (ref "U3") (pin "12") (pinfunction "+IN_12") (pintype "input"))
    )
    (net (code "84") (name "W4") (class "Default")
      (node (ref "R39") (pin "1") (pinfunction "1_1") (pintype "passive"))
      (node (ref "U$5") (pin "2") (pinfunction "2_2") (pintype "bidirectional"))
      (node (ref "U4") (pin "3") (pinfunction "+IN_3") (pintype "input"))
    )
    (net (code "85") (name "W5") (class "Default")
      (node (ref "R25") (pin "1") (pinfunction "1_1") (pintype "passive"))
      (node (ref "U$6") (pin "2") (pinfunction "2_2") (pintype "bidirectional"))
      (node (ref "U4") (pin "12") (pinfunction "+IN_12") (pintype "input"))
    )
    (net (code "86") (name "W6") (class "Default")
      (node (ref "R41") (pin "1") (pinfunction "1_1") (pintype "passive"))
      (node (ref "U$7") (pin "2") (pinfunction "2_2") (pintype "bidirectional"))
      (node (ref "U5") (pin "3") (pinfunction "+IN_3") (pintype "input"))
    )
    (net (code "87") (name "W7") (class "Default")
      (node (ref "R27") (pin "1") (pinfunction "1_1") (pintype "passive"))
      (node (ref "U$8") (pin "2") (pinfunction "2_2") (pintype "bidirectional"))
      (node (ref "U5") (pin "12") (pinfunction "+IN_12") (pintype "input"))
    )
    (net (code "88") (name "W8") (class "Default")
      (node (ref "R43") (pin "1") (pinfunction "1_1") (pintype "passive"))
      (node (ref "U$9") (pin "2") (pinfunction "2_2") (pintype "bidirectional"))
      (node (ref "U6") (pin "3") (pinfunction "+IN_3") (pintype "input"))
    )
    (net (code "89") (name "W9") (class "Default")
      (node (ref "R29") (pin "1") (pinfunction "1_1") (pintype "passive"))
      (node (ref "U$10") (pin "2") (pinfunction "2_2") (pintype "bidirectional"))
      (node (ref "U6") (pin "12") (pinfunction "+IN_12") (pintype "input"))
    )
    (net (code "90") (name "W10") (class "Default")
      (node (ref "R45") (pin "1") (pinfunction "1_1") (pintype "passive"))
      (node (ref "U$11") (pin "2") (pinfunction "2_2") (pintype "bidirectional"))
      (node (ref "U7") (pin "3") (pinfunction "+IN_3") (pintype "input"))
    )
    (net (code "91") (name "W11") (class "Default")
      (node (ref "R31") (pin "1") (pinfunction "1_1") (pintype "passive"))
      (node (ref "U$12") (pin "2") (pinfunction "2_2") (pintype "bidirectional"))
      (node (ref "U7") (pin "12") (pinfunction "+IN_12") (pintype "input"))
    )
    (net (code "92") (name "W12") (class "Default")
      (node (ref "R47") (pin "1") (pinfunction "1_1") (pintype "passive"))
      (node (ref "U$13") (pin "2") (pinfunction "2_2") (pintype "bidirectional"))
      (node (ref "U8") (pin "3") (pinfunction "+IN_3") (pintype "input"))
    )
    (net (code "93") (name "W13") (class "Default")
      (node (ref "R33") (pin "1") (pinfunction "1_1") (pintype "passive"))
      (node (ref "U$14") (pin "2") (pinfunction "2_2") (pintype "bidirectional"))
      (node (ref "U8") (pin "12") (pinfunction "+IN_12") (pintype "input"))
    )
    (net (code "94") (name "W14") (class "Default")
      (node (ref "R50") (pin "1") (pinfunction "1_1") (pintype "passive"))
      (node (ref "U$15") (pin "2") (pinfunction "2_2") (pintype "bidirectional"))
      (node (ref "U9") (pin "3") (pinfunction "+IN_3") (pintype "input"))
    )
    (net (code "95") (name "W15") (class "Default")
      (node (ref "R19") (pin "1") (pinfunction "1_1") (pintype "passive"))
      (node (ref "U$16") (pin "2") (pinfunction "2_2") (pintype "bidirectional"))
      (node (ref "U9") (pin "12") (pinfunction "+IN_12") (pintype "input"))
    )
    (net (code "96") (name "unconnected-(J1-SWITCH-PadSW)") (class "Default")
      (node (ref "J1") (pin "SW") (pinfunction "SWITCH_SW") (pintype "passive"))
    )
    (net (code "97") (name "unconnected-(J2-SWITCH-PadSW)") (class "Default")
      (node (ref "J2") (pin "SW") (pinfunction "SWITCH_SW") (pintype "passive"))
    )
    (net (code "98") (name "unconnected-(J3-SWITCH-PadSW)") (class "Default")
      (node (ref "J3") (pin "SW") (pinfunction "SWITCH_SW") (pintype "passive"))
    )
    (net (code "99") (name "unconnected-(J4-SWITCH-PadSW)") (class "Default")
      (node (ref "J4") (pin "SW") (pinfunction "SWITCH_SW") (pintype "passive"))
    )
    (net (code "100") (name "unconnected-(J5-SWITCH-PadSW)") (class "Default")
      (node (ref "J5") (pin "SW") (pinfunction "SWITCH_SW") (pintype "passive"))
    )
    (net (code "101") (name "unconnected-(J6-SWITCH-PadSW)") (class "Default")
      (node (ref "J6") (pin "SW") (pinfunction "SWITCH_SW") (pintype "passive"))
    )
    (net (code "102") (name "unconnected-(J7-SWITCH-PadSW)") (class "Default")
      (node (ref "J7") (pin "SW") (pinfunction "SWITCH_SW") (pintype "passive"))
    )
    (net (code "103") (name "unconnected-(J8-SWITCH-PadSW)") (class "Default")
      (node (ref "J8") (pin "SW") (pinfunction "SWITCH_SW") (pintype "passive"))
    )
    (net (code "104") (name "unconnected-(J9-SWITCH-PadSW)") (class "Default")
      (node (ref "J9") (pin "SW") (pinfunction "SWITCH_SW") (pintype "passive"))
    )
    (net (code "105") (name "unconnected-(J10-SWITCH-PadSW)") (class "Default")
      (node (ref "J10") (pin "SW") (pinfunction "SWITCH_SW") (pintype "passive"))
    )
    (net (code "106") (name "unconnected-(J11-SWITCH-PadSW)") (class "Default")
      (node (ref "J11") (pin "SW") (pinfunction "SWITCH_SW") (pintype "passive"))
    )
    (net (code "107") (name "unconnected-(J12-SWITCH-PadSW)") (class "Default")
      (node (ref "J12") (pin "SW") (pinfunction "SWITCH_SW") (pintype "passive"))
    )
    (net (code "108") (name "unconnected-(J13-SWITCH-PadSW)") (class "Default")
      (node (ref "J13") (pin "SW") (pinfunction "SWITCH_SW") (pintype "passive"))
    )
    (net (code "109") (name "unconnected-(J14-SWITCH-PadSW)") (class "Default")
      (node (ref "J14") (pin "SW") (pinfunction "SWITCH_SW") (pintype "passive"))
    )
    (net (code "110") (name "unconnected-(J15-SWITCH-PadSW)") (class "Default")
      (node (ref "J15") (pin "SW") (pinfunction "SWITCH_SW") (pintype "passive"))
    )
    (net (code "111") (name "unconnected-(J16-SWITCH-PadSW)") (class "Default")
      (node (ref "J16") (pin "SW") (pinfunction "SWITCH_SW") (pintype "passive"))
    )
    (net (code "112") (name "unconnected-(U$17-0{slash}RX1{slash}T-Pad0)") (class "Default")
      (node (ref "U$17") (pin "0") (pinfunction "0/RX1/T_0") (pintype "bidirectional"))
    )
    (net (code "113") (name "unconnected-(U$17-3{slash}CAN-TX{slash}PWM-Pad3)") (class "Default")
      (node (ref "U$17") (pin "3") (pinfunction "3/CAN-TX/PWM_3") (pintype "bidirectional"))
    )
    (net (code "114") (name "unconnected-(U$17-4{slash}CAN-RX{slash}PWM-Pad4)") (class "Default")
      (node (ref "U$17") (pin "4") (pinfunction "4/CAN-RX/PWM_4") (pintype "bidirectional"))
    )
    (net (code "115") (name "unconnected-(U$17-9{slash}RX2{slash}PWM-Pad9)") (class "Default")
      (node (ref "U$17") (pin "9") (pinfunction "9/RX2/PWM_9") (pintype "bidirectional"))
    )
    (net (code "116") (name "unconnected-(U$17-10{slash}TX2{slash}PWM-Pad10)") (class "Default")
      (node (ref "U$17") (pin "10") (pinfunction "10/TX2/PWM_10") (pintype "bidirectional"))
    )
    (net (code "117") (name "unconnected-(U$17-11{slash}MOSI-Pad11)") (class "Default")
      (node (ref "U$17") (pin "11") (pinfunction "11/MOSI_11") (pintype "bidirectional"))
    )
    (net (code "118") (name "unconnected-(U$17-12{slash}MISO-Pad12)") (class "Default")
      (node (ref "U$17") (pin "12") (pinfunction "12/MISO_12") (pintype "bidirectional"))
    )
    (net (code "119") (name "unconnected-(U$17-13{slash}SCK{slash}LED-Pad13)") (class "Default")
      (node (ref "U$17") (pin "13") (pinfunction "13/SCK/LED_13") (pintype "bidirectional"))
    )
    (net (code "120") (name "unconnected-(U$17-15{slash}A1{slash}T-Pad15{slash}A1)") (class "Default")
      (node (ref "U$17") (pin "15/A1") (pinfunction "15/A1/T_15/A1") (pintype "bidirectional"))
    )
    (net (code "121") (name "unconnected-(U$17-16{slash}A2{slash}T-Pad16{slash}A2)") (class "Default")
      (node (ref "U$17") (pin "16/A2") (pinfunction "16/A2/T_16/A2") (pintype "bidirectional"))
    )
    (net (code "122") (name "unconnected-(U$17-17{slash}A3{slash}T-Pad17{slash}A3)") (class "Default")
      (node (ref "U$17") (pin "17/A3") (pinfunction "17/A3/T_17/A3") (pintype "bidirectional"))
    )
    (net (code "123") (name "unconnected-(U$17-20{slash}A6{slash}PWM-Pad20{slash}A6)") (class "Default")
      (node (ref "U$17") (pin "20/A6") (pinfunction "20/A6/PWM_20/A6") (pintype "bidirectional"))
    )
    (net (code "124") (name "unconnected-(U$17-21{slash}A7{slash}PWM-Pad21{slash}A7)") (class "Default")
      (node (ref "U$17") (pin "21/A7") (pinfunction "21/A7/PWM_21/A7") (pintype "bidirectional"))
    )
    (net (code "125") (name "unconnected-(U$17-22{slash}A8{slash}T{slash}PWM-Pad22{slash}A8)") (class "Default")
      (node (ref "U$17") (pin "22/A8") (pinfunction "22/A8/T/PWM_22/A8") (pintype "bidirectional"))
    )
    (net (code "126") (name "unconnected-(U$17-23{slash}A9{slash}T{slash}PWM-Pad23{slash}A9)") (class "Default")
      (node (ref "U$17") (pin "23/A9") (pinfunction "23/A9/T/PWM_23/A9") (pintype "bidirectional"))
    )
    (net (code "127") (name "unconnected-(U$17-Pad2)") (class "Default")
      (node (ref "U$17") (pin "2") (pinfunction "2_2") (pintype "bidirectional"))
    )
  )
)
